# STM32.net
KiCad netlist of a schematic drawn in Altium Designer
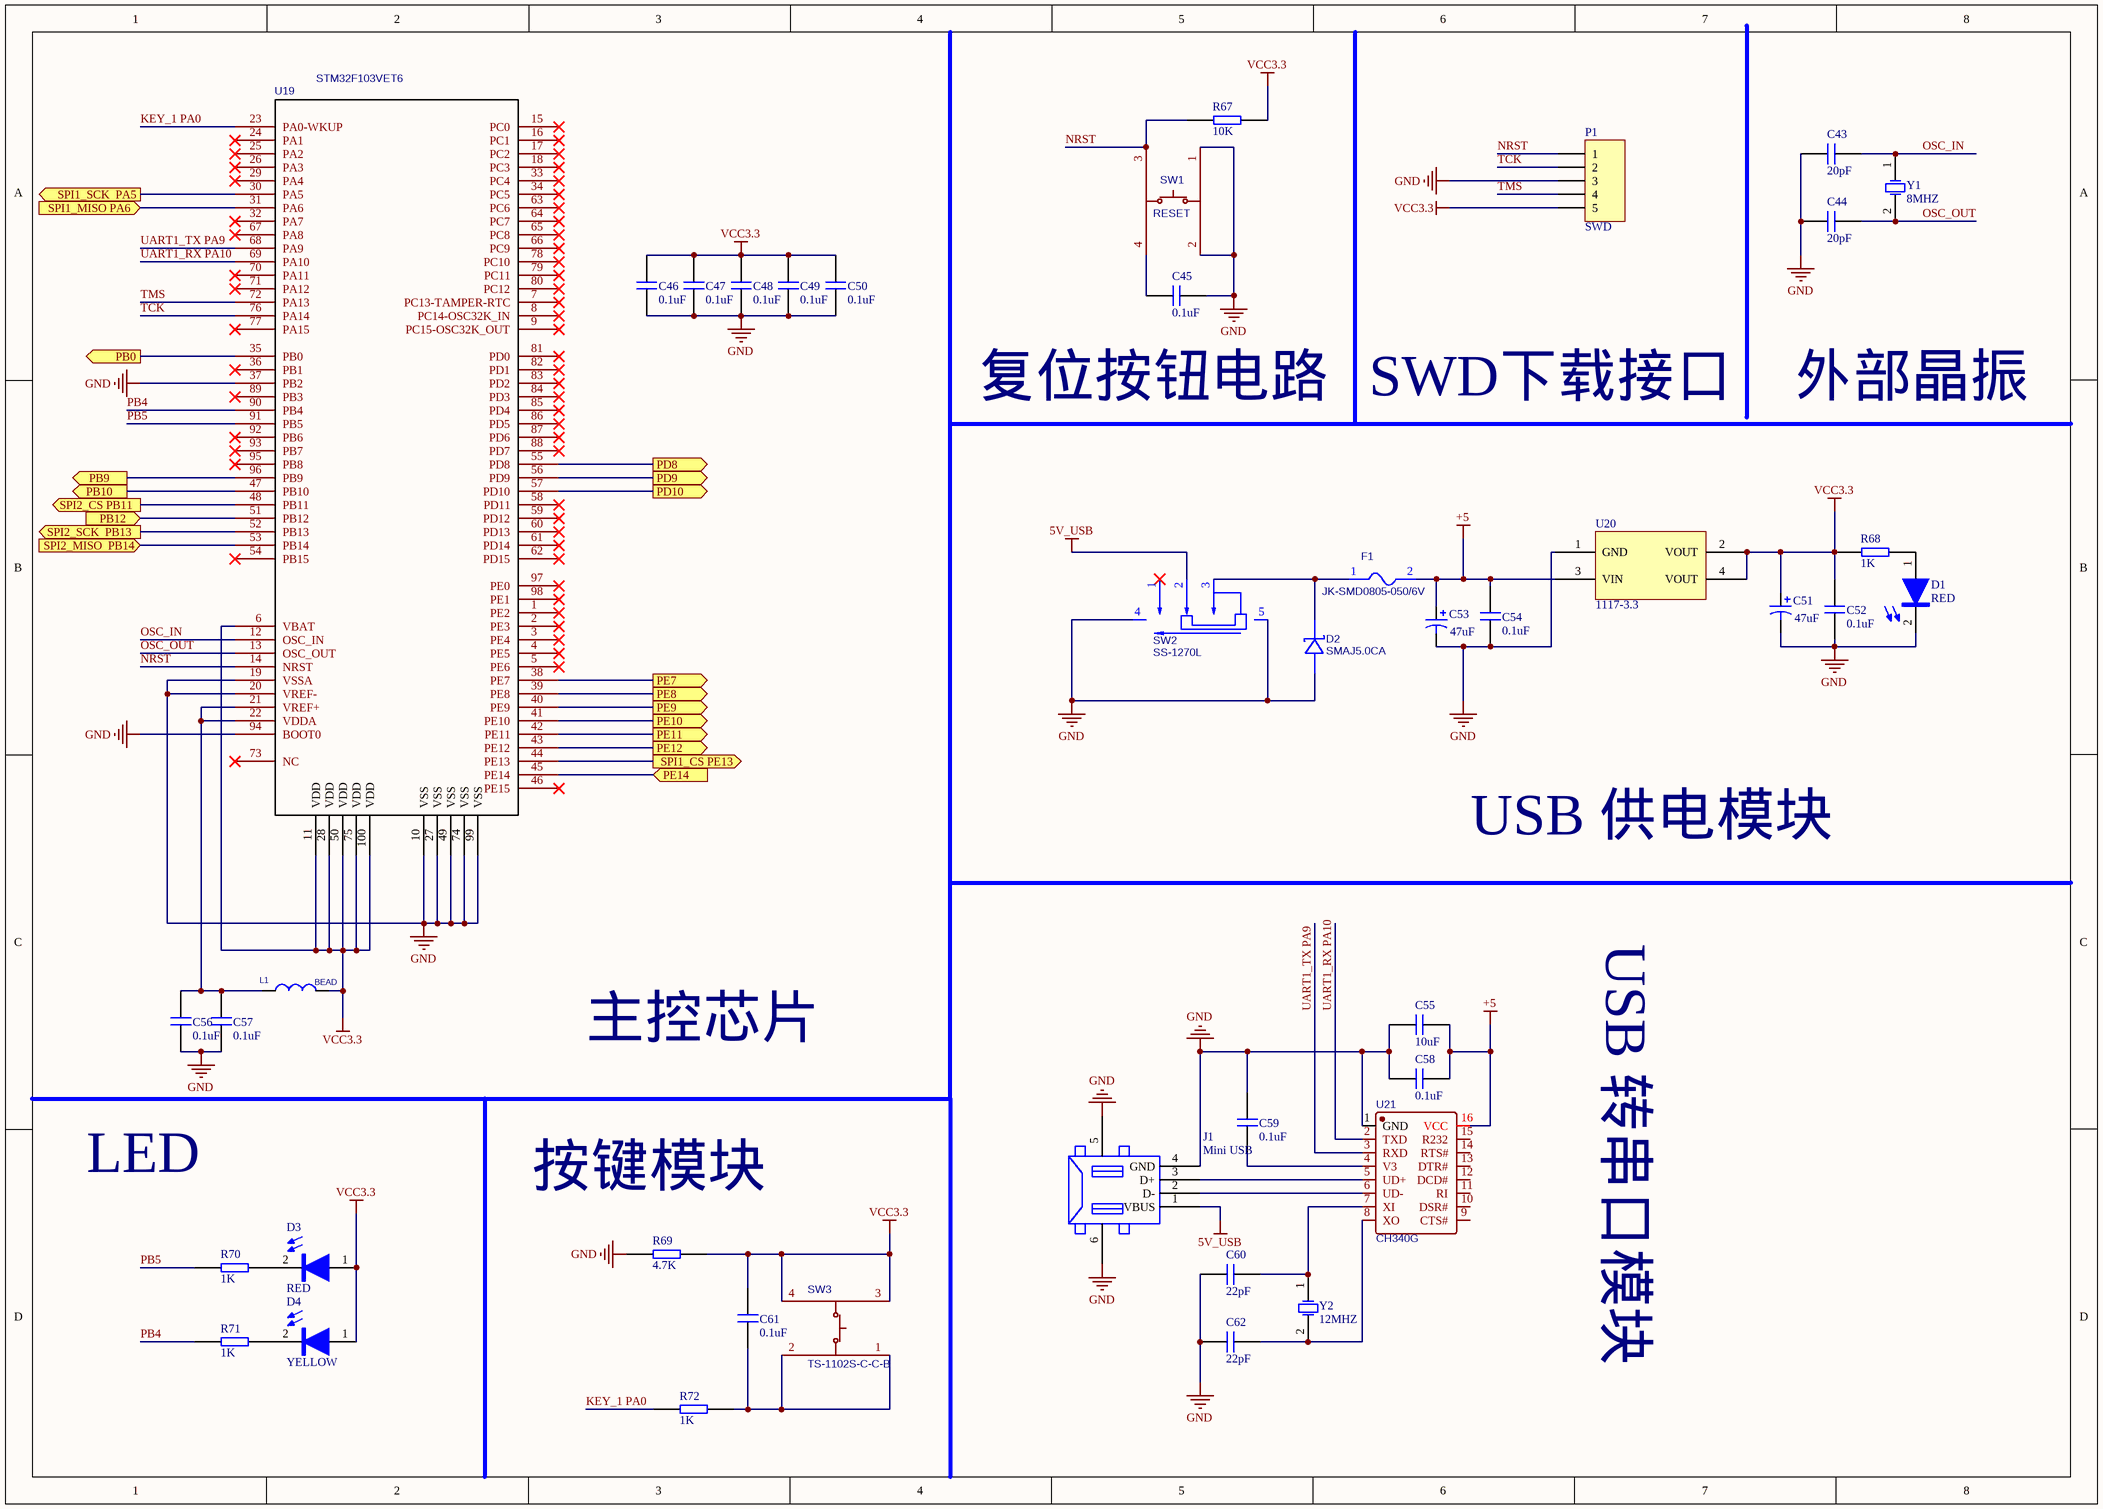
[diagram p0: STM32主控模块.SchDoc]

(export (version "E")
  (design (tool "Eeschema 10.0.6"))
  (components
    (comp (ref "C43")
      (value "20pF")
      (footprint "0805C")
      (description "NPO高频电容")
      (libsource (lib "毕业设计") (part "CAP"))
    )
    (comp (ref "C44")
      (value "20pF")
      (footprint "0805C")
      (description "NPO高频电容")
      (libsource (lib "毕业设计") (part "CAP"))
    )
    (comp (ref "C45")
      (value "0.1uF")
      (footprint "0805C")
      (description "普通电容")
      (libsource (lib "毕业设计") (part "CAP"))
    )
    (comp (ref "C46")
      (value "0.1uF")
      (footprint "0805C")
      (description "普通电容")
      (libsource (lib "毕业设计") (part "CAP"))
    )
    (comp (ref "C47")
      (value "0.1uF")
      (footprint "0805C")
      (description "普通电容")
      (libsource (lib "毕业设计") (part "CAP"))
    )
    (comp (ref "C48")
      (value "0.1uF")
      (footprint "0805C")
      (description "普通电容")
      (libsource (lib "毕业设计") (part "CAP"))
    )
    (comp (ref "C49")
      (value "0.1uF")
      (footprint "0805C")
      (description "普通电容")
      (libsource (lib "毕业设计") (part "CAP"))
    )
    (comp (ref "C50")
      (value "0.1uF")
      (footprint "0805C")
      (description "普通电容")
      (libsource (lib "毕业设计") (part "CAP"))
    )
    (comp (ref "C51")
      (value "47uF")
      (footprint "CAP-SMD_BD6.3-L6.6-W6.6-LS7.2-FD")
      (description "Polarized Capacitor (Radial)")
      (fields (field (name "Comment") "Cap Pol1") (field (name "PUBLISHER") "Altium Limited"))
      (libsource (lib "Miscellaneous Devices") (part "Cap Pol1"))
    )
    (comp (ref "C52")
      (value "0.1uF")
      (footprint "0805C")
      (description "普通电容")
      (libsource (lib "毕业设计") (part "CAP"))
    )
    (comp (ref "C53")
      (value "47uF")
      (footprint "CAP-SMD_BD6.3-L6.6-W6.6-LS7.2-FD")
      (description "Polarized Capacitor (Radial)")
      (fields (field (name "Comment") "Cap Pol1") (field (name "PUBLISHER") "Altium Limited"))
      (libsource (lib "Miscellaneous Devices") (part "Cap Pol1"))
    )
    (comp (ref "C54")
      (value "0.1uF")
      (footprint "0805C")
      (description "普通电容")
      (libsource (lib "毕业设计") (part "CAP"))
    )
    (comp (ref "C55")
      (value "10uF")
      (footprint "0805C")
      (description "普通电容")
      (libsource (lib "毕业设计") (part "CAP"))
    )
    (comp (ref "C56")
      (value "0.1uF")
      (footprint "0805C")
      (description "普通电容")
      (libsource (lib "毕业设计") (part "CAP"))
    )
    (comp (ref "C57")
      (value "0.1uF")
      (footprint "0805C")
      (description "普通电容")
      (libsource (lib "毕业设计") (part "CAP"))
    )
    (comp (ref "C58")
      (value "0.1uF")
      (footprint "0805C")
      (description "普通电容")
      (libsource (lib "毕业设计") (part "CAP"))
    )
    (comp (ref "C59")
      (value "0.1uF")
      (footprint "0805C")
      (description "普通电容")
      (libsource (lib "毕业设计") (part "CAP"))
    )
    (comp (ref "C60")
      (value "22pF")
      (footprint "0603C")
      (description "普通电容")
      (libsource (lib "毕业设计") (part "CAP"))
    )
    (comp (ref "C61")
      (value "0.1uF")
      (footprint "0805C")
      (description "普通电容")
      (libsource (lib "毕业设计") (part "CAP"))
    )
    (comp (ref "C62")
      (value "22pF")
      (footprint "0603C")
      (description "普通电容")
      (libsource (lib "毕业设计") (part "CAP"))
    )
    (comp (ref "D1")
      (value "RED")
      (footprint "LED0603")
      (description "发光二极管")
      (libsource (lib "毕业设计") (part "LED"))
    )
    (comp (ref "D2")
      (value "SMAJ5.0CA")
      (footprint "SMA_L4.4-W2.6-LS5.0-RD")
      (description "稳压二极管")
      (fields (field (name "BOM_SUPPLIER PART") "C116601"))
      (libsource (lib "毕业设计") (part "SMAJ5.0CA_C116601"))
    )
    (comp (ref "D3")
      (value "RED")
      (footprint "LED0603")
      (description "发光二极管")
      (libsource (lib "毕业设计") (part "LED"))
    )
    (comp (ref "D4")
      (value "YELLOW")
      (footprint "LED0603")
      (description "发光二极管")
      (libsource (lib "毕业设计") (part "LED"))
    )
    (comp (ref "F1")
      (value "JK-SMD0805-050/6V")
      (footprint "F0805")
      (description "500mA 保险丝")
      (fields (field (name "BOM_SUPPLIER PART") "C2830231") (field (name "CONTRIBUTOR") "LCSC"))
      (libsource (lib "毕业设计") (part "JK-SMD0805-050/6V"))
    )
    (comp (ref "J1")
      (value "Mini USB")
      (footprint "USB-B-TH_U241-041N-1BR85-1")
      (description "Mini A型USB母座")
      (libsource (lib "毕业设计") (part "Mini-B USB H"))
    )
    (comp (ref "L1")
      (value "BEAD")
      (footprint "L0603")
      (description "0603,BEAD")
      (fields (field (name "Comment") "BEAD-220/100MHZ-0603"))
      (libsource (lib "毕业设计") (part "BEAD-220/100MHZ-0603"))
    )
    (comp (ref "P1")
      (value "SWD")
      (footprint "HDR1X5")
      (description "Header, 5-Pin")
      (fields (field (name "PUBLISHER") "Altium Limited"))
      (libsource (lib "Miscellaneous Connectors") (part "Header 5"))
    )
    (comp (ref "R67")
      (value "10K")
      (footprint "0603R")
      (description "电阻模型")
      (libsource (lib "毕业设计") (part "RES"))
    )
    (comp (ref "R68")
      (value "1K")
      (footprint "0805R")
      (description "电阻模型")
      (libsource (lib "毕业设计") (part "RES"))
    )
    (comp (ref "R69")
      (value "4.7K")
      (footprint "0603R")
      (description "电阻模型")
      (libsource (lib "毕业设计") (part "RES"))
    )
    (comp (ref "R70")
      (value "1K")
      (footprint "0805R")
      (description "电阻模型")
      (libsource (lib "毕业设计") (part "RES"))
    )
    (comp (ref "R71")
      (value "1K")
      (footprint "0805R")
      (description "电阻模型")
      (libsource (lib "毕业设计") (part "RES"))
    )
    (comp (ref "R72")
      (value "1K")
      (footprint "0805R")
      (description "电阻模型")
      (libsource (lib "毕业设计") (part "RES"))
    )
    (comp (ref "SW1")
      (value "RESET")
      (footprint "KEY-SMD_4P-L6.0-W6.0-P4.50-LS9.5-BL")
      (description "轻触开关")
      (fields
        (field (name "BOM_SUPPLIER PART") "C381039")
        (field (name "BOM_MANUFACTURER PART") "TS-1102S-C-C-B")
        (field (name "CONTRIBUTOR") "LCSC")
      )
      (libsource (lib "毕业设计") (part "SW-PB"))
    )
    (comp (ref "SW2")
      (value "SS-1270L")
      (footprint "SW-TH_SLD-12-501")
      (description "拨动开关")
      (fields (field (name "BOM_SUPPLIER PART") "C589300") (field (name "CONTRIBUTOR") "LCSC"))
      (libsource (lib "毕业设计") (part "SS-1270L"))
    )
    (comp (ref "SW3")
      (value "TS-1102S-C-C-B")
      (footprint "KEY-SMD_4P-L6.0-W6.0-P4.50-LS9.5-BL")
      (description "轻触开关")
      (fields (field (name "BOM_SUPPLIER PART") "C381039") (field (name "CONTRIBUTOR") "LCSC"))
      (libsource (lib "毕业设计") (part "SW-PB"))
    )
    (comp (ref "U19")
      (value "STM32F103VET6")
      (footprint "STM32F103VET6-LQFP")
      (fields (field (name "BOM_SUPPLIER PART") "C8308"))
      (libsource (lib "毕业设计") (part "STM32F103VET6"))
    )
    (comp (ref "U20")
      (value "1117-3.3")
      (footprint "SOT230P700X190-4N")
      (description "线性稳压芯片")
      (libsource (lib "毕业设计") (part "AMS1117-3.3"))
    )
    (comp (ref "U21")
      (value "CH340G")
      (footprint "SOIC-16_L9.9-W3.9-P1.27-LS6.0-BL")
      (description "USB转TTL芯片")
      (fields (field (name "BOM_SUPPLIER PART") "C14267"))
      (libsource (lib "毕业设计") (part "CH340G"))
    )
    (comp (ref "Y1")
      (value "8MHZ")
      (footprint "49SMD")
      (description "Crystal Oscillator")
      (fields (field (name "PUBLISHER") "Altium Limited"))
      (libsource (lib "Miscellaneous Devices") (part "XTAL"))
    )
    (comp (ref "Y2")
      (value "12MHZ")
      (footprint "HC-49US_L11.5-W4.5-P4.88")
      (description "Crystal Oscillator")
      (fields (field (name "PUBLISHER") "Altium Limited"))
      (libsource (lib "Miscellaneous Devices") (part "XTAL"))
    )
  )
  (nets
    (net (code "1") (name "+5") (class "Default")
      (node (ref "C53") (pin "1") (pinfunction "1_1") (pintype "passive"))
      (node (ref "C54") (pin "2") (pinfunction "2_2") (pintype "passive"))
      (node (ref "C55") (pin "1") (pinfunction "1_1") (pintype "passive"))
      (node (ref "C58") (pin "2") (pinfunction "2_2") (pintype "passive"))
      (node (ref "F1") (pin "2") (pinfunction "2_2") (pintype "passive"))
      (node (ref "U20") (pin "3") (pinfunction "VIN_3") (pintype "passive"))
      (node (ref "U21") (pin "16") (pinfunction "VCC_16") (pintype "passive"))
    )
    (net (code "2") (name "/KEY_1 PA0") (class "Default")
      (node (ref "R72") (pin "1") (pinfunction "1_1") (pintype "passive"))
      (node (ref "U19") (pin "23") (pinfunction "PA0-WKUP_23") (pintype "passive"))
    )
    (net (code "3") (name "/NRST") (class "Default")
      (node (ref "P1") (pin "1") (pinfunction "1_1") (pintype "passive"))
      (node (ref "R67") (pin "1") (pinfunction "1_1") (pintype "passive"))
      (node (ref "SW1") (pin "3") (pinfunction "3_3") (pintype "passive"))
      (node (ref "U19") (pin "14") (pinfunction "NRST_14") (pintype "passive"))
    )
    (net (code "4") (name "/OSC_IN") (class "Default")
      (node (ref "C43") (pin "2") (pinfunction "2_2") (pintype "passive"))
      (node (ref "U19") (pin "12") (pinfunction "OSC_IN_12") (pintype "passive"))
      (node (ref "Y1") (pin "1") (pinfunction "OSC1_1") (pintype "passive"))
    )
    (net (code "5") (name "/OSC_OUT") (class "Default")
      (node (ref "C44") (pin "2") (pinfunction "2_2") (pintype "passive"))
      (node (ref "U19") (pin "13") (pinfunction "OSC_OUT_13") (pintype "passive"))
      (node (ref "Y1") (pin "2") (pinfunction "OSC2_2") (pintype "passive"))
    )
    (net (code "6") (name "/PB0") (class "Default")
      (node (ref "U19") (pin "35") (pinfunction "PB0_35") (pintype "passive"))
    )
    (net (code "7") (name "/PB4") (class "Default")
      (node (ref "R71") (pin "1") (pinfunction "1_1") (pintype "passive"))
      (node (ref "U19") (pin "90") (pinfunction "PB4_90") (pintype "passive"))
    )
    (net (code "8") (name "/PB5") (class "Default")
      (node (ref "R70") (pin "1") (pinfunction "1_1") (pintype "passive"))
      (node (ref "U19") (pin "91") (pinfunction "PB5_91") (pintype "passive"))
    )
    (net (code "9") (name "/PB9") (class "Default")
      (node (ref "U19") (pin "96") (pinfunction "PB9_96") (pintype "passive"))
    )
    (net (code "10") (name "/PB10") (class "Default")
      (node (ref "U19") (pin "47") (pinfunction "PB10_47") (pintype "passive"))
    )
    (net (code "11") (name "/PB12") (class "Default")
      (node (ref "U19") (pin "51") (pinfunction "PB12_51") (pintype "passive"))
    )
    (net (code "12") (name "/PD8") (class "Default")
      (node (ref "U19") (pin "55") (pinfunction "PD8_55") (pintype "passive"))
    )
    (net (code "13") (name "/PD9") (class "Default")
      (node (ref "U19") (pin "56") (pinfunction "PD9_56") (pintype "passive"))
    )
    (net (code "14") (name "/PD10") (class "Default")
      (node (ref "U19") (pin "57") (pinfunction "PD10_57") (pintype "passive"))
    )
    (net (code "15") (name "/PE7") (class "Default")
      (node (ref "U19") (pin "38") (pinfunction "PE7_38") (pintype "passive"))
    )
    (net (code "16") (name "/PE8") (class "Default")
      (node (ref "U19") (pin "39") (pinfunction "PE8_39") (pintype "passive"))
    )
    (net (code "17") (name "/PE9") (class "Default")
      (node (ref "U19") (pin "40") (pinfunction "PE9_40") (pintype "passive"))
    )
    (net (code "18") (name "/PE10") (class "Default")
      (node (ref "U19") (pin "41") (pinfunction "PE10_41") (pintype "passive"))
    )
    (net (code "19") (name "/PE11") (class "Default")
      (node (ref "U19") (pin "42") (pinfunction "PE11_42") (pintype "passive"))
    )
    (net (code "20") (name "/PE12") (class "Default")
      (node (ref "U19") (pin "43") (pinfunction "PE12_43") (pintype "passive"))
    )
    (net (code "21") (name "/PE14") (class "Default")
      (node (ref "U19") (pin "45") (pinfunction "PE14_45") (pintype "passive"))
    )
    (net (code "22") (name "/SPI1_CS PE13") (class "Default")
      (node (ref "U19") (pin "44") (pinfunction "PE13_44") (pintype "passive"))
    )
    (net (code "23") (name "/SPI1_MISO PA6") (class "Default")
      (node (ref "U19") (pin "31") (pinfunction "PA6_31") (pintype "passive"))
    )
    (net (code "24") (name "/SPI1_SCK  PA5") (class "Default")
      (node (ref "U19") (pin "30") (pinfunction "PA5_30") (pintype "passive"))
    )
    (net (code "25") (name "/SPI2_CS PB11") (class "Default")
      (node (ref "U19") (pin "48") (pinfunction "PB11_48") (pintype "passive"))
    )
    (net (code "26") (name "/SPI2_MISO  PB14") (class "Default")
      (node (ref "U19") (pin "53") (pinfunction "PB14_53") (pintype "passive"))
    )
    (net (code "27") (name "/SPI2_SCK  PB13") (class "Default")
      (node (ref "U19") (pin "52") (pinfunction "PB13_52") (pintype "passive"))
    )
    (net (code "28") (name "/TCK") (class "Default")
      (node (ref "P1") (pin "2") (pinfunction "2_2") (pintype "passive"))
      (node (ref "U19") (pin "76") (pinfunction "PA14_76") (pintype "passive"))
    )
    (net (code "29") (name "/TMS") (class "Default")
      (node (ref "P1") (pin "4") (pinfunction "4_4") (pintype "passive"))
      (node (ref "U19") (pin "72") (pinfunction "PA13_72") (pintype "passive"))
    )
    (net (code "30") (name "/UART1_RX PA10") (class "Default")
      (node (ref "U19") (pin "69") (pinfunction "PA10_69") (pintype "passive"))
      (node (ref "U21") (pin "2") (pinfunction "TXD_2") (pintype "passive"))
    )
    (net (code "31") (name "/UART1_TX PA9") (class "Default")
      (node (ref "U19") (pin "68") (pinfunction "PA9_68") (pintype "passive"))
      (node (ref "U21") (pin "3") (pinfunction "RXD_3") (pintype "passive"))
    )
    (net (code "32") (name "5V_USB") (class "Default")
      (node (ref "J1") (pin "1") (pinfunction "VBUS_1") (pintype "passive"))
      (node (ref "SW2") (pin "2") (pinfunction "2_2") (pintype "passive"))
    )
    (net (code "33") (name "GND") (class "Default")
      (node (ref "C43") (pin "1") (pinfunction "1_1") (pintype "passive"))
      (node (ref "C44") (pin "1") (pinfunction "1_1") (pintype "passive"))
      (node (ref "C45") (pin "2") (pinfunction "2_2") (pintype "passive"))
      (node (ref "C46") (pin "1") (pinfunction "1_1") (pintype "passive"))
      (node (ref "C47") (pin "1") (pinfunction "1_1") (pintype "passive"))
      (node (ref "C48") (pin "1") (pinfunction "1_1") (pintype "passive"))
      (node (ref "C49") (pin "1") (pinfunction "1_1") (pintype "passive"))
      (node (ref "C50") (pin "1") (pinfunction "1_1") (pintype "passive"))
      (node (ref "C51") (pin "2") (pinfunction "2_2") (pintype "passive"))
      (node (ref "C52") (pin "1") (pinfunction "1_1") (pintype "passive"))
      (node (ref "C53") (pin "2") (pinfunction "2_2") (pintype "passive"))
      (node (ref "C54") (pin "1") (pinfunction "1_1") (pintype "passive"))
      (node (ref "C55") (pin "2") (pinfunction "2_2") (pintype "passive"))
      (node (ref "C56") (pin "1") (pinfunction "1_1") (pintype "passive"))
      (node (ref "C57") (pin "1") (pinfunction "1_1") (pintype "passive"))
      (node (ref "C58") (pin "1") (pinfunction "1_1") (pintype "passive"))
      (node (ref "C59") (pin "1") (pinfunction "1_1") (pintype "passive"))
      (node (ref "C60") (pin "1") (pinfunction "1_1") (pintype "passive"))
      (node (ref "C62") (pin "1") (pinfunction "1_1") (pintype "passive"))
      (node (ref "D1") (pin "2") (pinfunction "2_2") (pintype "passive"))
      (node (ref "D2") (pin "2") (pinfunction "A_2") (pintype "passive"))
      (node (ref "J1") (pin "4") (pinfunction "GND_4") (pintype "passive"))
      (node (ref "J1") (pin "5") (pintype "passive"))
      (node (ref "J1") (pin "6") (pintype "passive"))
      (node (ref "P1") (pin "3") (pinfunction "3_3") (pintype "passive"))
      (node (ref "R69") (pin "1") (pinfunction "1_1") (pintype "passive"))
      (node (ref "SW1") (pin "1") (pinfunction "1_1") (pintype "passive"))
      (node (ref "SW1") (pin "2") (pinfunction "2_2") (pintype "passive"))
      (node (ref "SW2") (pin "4") (pinfunction "4_4") (pintype "passive"))
      (node (ref "SW2") (pin "5") (pinfunction "5_5") (pintype "passive"))
      (node (ref "U19") (pin "10") (pinfunction "VSS_10") (pintype "passive"))
      (node (ref "U19") (pin "19") (pinfunction "VSSA_19") (pintype "passive"))
      (node (ref "U19") (pin "20") (pinfunction "VREF-_20") (pintype "passive"))
      (node (ref "U19") (pin "27") (pinfunction "VSS_27") (pintype "passive"))
      (node (ref "U19") (pin "37") (pinfunction "PB2_37") (pintype "passive"))
      (node (ref "U19") (pin "49") (pinfunction "VSS_49") (pintype "passive"))
      (node (ref "U19") (pin "74") (pinfunction "VSS_74") (pintype "passive"))
      (node (ref "U19") (pin "94") (pinfunction "BOOT0_94") (pintype "passive"))
      (node (ref "U19") (pin "99") (pinfunction "VSS_99") (pintype "passive"))
      (node (ref "U20") (pin "1") (pinfunction "GND_1") (pintype "passive"))
      (node (ref "U21") (pin "1") (pinfunction "GND_1") (pintype "passive"))
    )
    (net (code "34") (name "Net-(C45-Pad1)") (class "Default")
      (node (ref "C45") (pin "1") (pinfunction "1_1") (pintype "passive"))
      (node (ref "SW1") (pin "4") (pinfunction "4_4") (pintype "passive"))
    )
    (net (code "35") (name "Net-(C61-Pad1)") (class "Default")
      (node (ref "C61") (pin "1") (pinfunction "1_1") (pintype "passive"))
      (node (ref "R72") (pin "2") (pinfunction "2_2") (pintype "passive"))
      (node (ref "SW3") (pin "1") (pinfunction "1_1") (pintype "passive"))
      (node (ref "SW3") (pin "2") (pinfunction "2_2") (pintype "passive"))
    )
    (net (code "36") (name "Net-(D1-Pad1)") (class "Default")
      (node (ref "D1") (pin "1") (pinfunction "1_1") (pintype "passive"))
      (node (ref "R68") (pin "2") (pinfunction "2_2") (pintype "passive"))
    )
    (net (code "37") (name "Net-(D2-K)") (class "Default")
      (node (ref "D2") (pin "1") (pinfunction "K_1") (pintype "passive"))
      (node (ref "F1") (pin "1") (pinfunction "1_1") (pintype "passive"))
      (node (ref "SW2") (pin "3") (pinfunction "3_3") (pintype "passive"))
    )
    (net (code "38") (name "Net-(D3-Pad2)") (class "Default")
      (node (ref "D3") (pin "2") (pinfunction "2_2") (pintype "passive"))
      (node (ref "R70") (pin "2") (pinfunction "2_2") (pintype "passive"))
    )
    (net (code "39") (name "Net-(D4-Pad2)") (class "Default")
      (node (ref "D4") (pin "2") (pinfunction "2_2") (pintype "passive"))
      (node (ref "R71") (pin "2") (pinfunction "2_2") (pintype "passive"))
    )
    (net (code "40") (name "Net-(J1-D+)") (class "Default")
      (node (ref "J1") (pin "3") (pinfunction "D+_3") (pintype "passive"))
      (node (ref "U21") (pin "5") (pinfunction "UD+_5") (pintype "passive"))
    )
    (net (code "41") (name "Net-(J1-D-)") (class "Default")
      (node (ref "J1") (pin "2") (pinfunction "D-_2") (pintype "passive"))
      (node (ref "U21") (pin "6") (pinfunction "UD-_6") (pintype "passive"))
    )
    (net (code "42") (name "Net-(U19-VDDA)") (class "Default")
      (node (ref "C56") (pin "2") (pinfunction "2_2") (pintype "passive"))
      (node (ref "C57") (pin "2") (pinfunction "2_2") (pintype "passive"))
      (node (ref "L1") (pin "1") (pinfunction "1_1") (pintype "passive"))
      (node (ref "U19") (pin "21") (pinfunction "VREF+_21") (pintype "passive"))
      (node (ref "U19") (pin "22") (pinfunction "VDDA_22") (pintype "passive"))
    )
    (net (code "43") (name "Net-(U21-V3)") (class "Default")
      (node (ref "C59") (pin "2") (pinfunction "2_2") (pintype "passive"))
      (node (ref "U21") (pin "4") (pinfunction "V3_4") (pintype "passive"))
    )
    (net (code "44") (name "Net-(U21-XI)") (class "Default")
      (node (ref "C60") (pin "2") (pinfunction "2_2") (pintype "passive"))
      (node (ref "U21") (pin "7") (pinfunction "XI_7") (pintype "passive"))
      (node (ref "Y2") (pin "1") (pinfunction "OSC1_1") (pintype "passive"))
    )
    (net (code "45") (name "Net-(U21-XO)") (class "Default")
      (node (ref "C62") (pin "2") (pinfunction "2_2") (pintype "passive"))
      (node (ref "U21") (pin "8") (pinfunction "XO_8") (pintype "passive"))
      (node (ref "Y2") (pin "2") (pinfunction "OSC2_2") (pintype "passive"))
    )
    (net (code "46") (name "VCC3.3") (class "Default")
      (node (ref "C46") (pin "2") (pinfunction "2_2") (pintype "passive"))
      (node (ref "C47") (pin "2") (pinfunction "2_2") (pintype "passive"))
      (node (ref "C48") (pin "2") (pinfunction "2_2") (pintype "passive"))
      (node (ref "C49") (pin "2") (pinfunction "2_2") (pintype "passive"))
      (node (ref "C50") (pin "2") (pinfunction "2_2") (pintype "passive"))
      (node (ref "C51") (pin "1") (pinfunction "1_1") (pintype "passive"))
      (node (ref "C52") (pin "2") (pinfunction "2_2") (pintype "passive"))
      (node (ref "C61") (pin "2") (pinfunction "2_2") (pintype "passive"))
      (node (ref "D3") (pin "1") (pinfunction "1_1") (pintype "passive"))
      (node (ref "D4") (pin "1") (pinfunction "1_1") (pintype "passive"))
      (node (ref "L1") (pin "2") (pinfunction "2_2") (pintype "passive"))
      (node (ref "P1") (pin "5") (pinfunction "5_5") (pintype "passive"))
      (node (ref "R67") (pin "2") (pinfunction "2_2") (pintype "passive"))
      (node (ref "R68") (pin "1") (pinfunction "1_1") (pintype "passive"))
      (node (ref "R69") (pin "2") (pinfunction "2_2") (pintype "passive"))
      (node (ref "SW3") (pin "3") (pinfunction "3_3") (pintype "passive"))
      (node (ref "SW3") (pin "4") (pinfunction "4_4") (pintype "passive"))
      (node (ref "U19") (pin "100") (pinfunction "VDD_100") (pintype "passive"))
      (node (ref "U19") (pin "11") (pinfunction "VDD_11") (pintype "passive"))
      (node (ref "U19") (pin "28") (pinfunction "VDD_28") (pintype "passive"))
      (node (ref "U19") (pin "50") (pinfunction "VDD_50") (pintype "passive"))
      (node (ref "U19") (pin "6") (pinfunction "VBAT_6") (pintype "passive"))
      (node (ref "U19") (pin "75") (pinfunction "VDD_75") (pintype "passive"))
      (node (ref "U20") (pin "2") (pinfunction "VOUT_2") (pintype "passive"))
      (node (ref "U20") (pin "4") (pinfunction "VOUT_4") (pintype "passive"))
    )
    (net (code "47") (name "unconnected-(SW2-Pad1)") (class "Default")
      (node (ref "SW2") (pin "1") (pinfunction "1_1") (pintype "passive+no_connect"))
    )
    (net (code "48") (name "unconnected-(U19-NC-Pad73)") (class "Default")
      (node (ref "U19") (pin "73") (pinfunction "NC_73") (pintype "passive+no_connect"))
    )
    (net (code "49") (name "unconnected-(U19-PA1-Pad24)") (class "Default")
      (node (ref "U19") (pin "24") (pinfunction "PA1_24") (pintype "passive+no_connect"))
    )
    (net (code "50") (name "unconnected-(U19-PA2-Pad25)") (class "Default")
      (node (ref "U19") (pin "25") (pinfunction "PA2_25") (pintype "passive+no_connect"))
    )
    (net (code "51") (name "unconnected-(U19-PA3-Pad26)") (class "Default")
      (node (ref "U19") (pin "26") (pinfunction "PA3_26") (pintype "passive+no_connect"))
    )
    (net (code "52") (name "unconnected-(U19-PA4-Pad29)") (class "Default")
      (node (ref "U19") (pin "29") (pinfunction "PA4_29") (pintype "passive+no_connect"))
    )
    (net (code "53") (name "unconnected-(U19-PA7-Pad32)") (class "Default")
      (node (ref "U19") (pin "32") (pinfunction "PA7_32") (pintype "passive+no_connect"))
    )
    (net (code "54") (name "unconnected-(U19-PA8-Pad67)") (class "Default")
      (node (ref "U19") (pin "67") (pinfunction "PA8_67") (pintype "passive+no_connect"))
    )
    (net (code "55") (name "unconnected-(U19-PA11-Pad70)") (class "Default")
      (node (ref "U19") (pin "70") (pinfunction "PA11_70") (pintype "passive+no_connect"))
    )
    (net (code "56") (name "unconnected-(U19-PA12-Pad71)") (class "Default")
      (node (ref "U19") (pin "71") (pinfunction "PA12_71") (pintype "passive+no_connect"))
    )
    (net (code "57") (name "unconnected-(U19-PA15-Pad77)") (class "Default")
      (node (ref "U19") (pin "77") (pinfunction "PA15_77") (pintype "passive+no_connect"))
    )
    (net (code "58") (name "unconnected-(U19-PB1-Pad36)") (class "Default")
      (node (ref "U19") (pin "36") (pinfunction "PB1_36") (pintype "passive+no_connect"))
    )
    (net (code "59") (name "unconnected-(U19-PB3-Pad89)") (class "Default")
      (node (ref "U19") (pin "89") (pinfunction "PB3_89") (pintype "passive+no_connect"))
    )
    (net (code "60") (name "unconnected-(U19-PB6-Pad92)") (class "Default")
      (node (ref "U19") (pin "92") (pinfunction "PB6_92") (pintype "passive+no_connect"))
    )
    (net (code "61") (name "unconnected-(U19-PB7-Pad93)") (class "Default")
      (node (ref "U19") (pin "93") (pinfunction "PB7_93") (pintype "passive+no_connect"))
    )
    (net (code "62") (name "unconnected-(U19-PB8-Pad95)") (class "Default")
      (node (ref "U19") (pin "95") (pinfunction "PB8_95") (pintype "passive+no_connect"))
    )
    (net (code "63") (name "unconnected-(U19-PB15-Pad54)") (class "Default")
      (node (ref "U19") (pin "54") (pinfunction "PB15_54") (pintype "passive+no_connect"))
    )
    (net (code "64") (name "unconnected-(U19-PC0-Pad15)") (class "Default")
      (node (ref "U19") (pin "15") (pinfunction "PC0_15") (pintype "passive+no_connect"))
    )
    (net (code "65") (name "unconnected-(U19-PC1-Pad16)") (class "Default")
      (node (ref "U19") (pin "16") (pinfunction "PC1_16") (pintype "passive+no_connect"))
    )
    (net (code "66") (name "unconnected-(U19-PC2-Pad17)") (class "Default")
      (node (ref "U19") (pin "17") (pinfunction "PC2_17") (pintype "passive+no_connect"))
    )
    (net (code "67") (name "unconnected-(U19-PC3-Pad18)") (class "Default")
      (node (ref "U19") (pin "18") (pinfunction "PC3_18") (pintype "passive+no_connect"))
    )
    (net (code "68") (name "unconnected-(U19-PC4-Pad33)") (class "Default")
      (node (ref "U19") (pin "33") (pinfunction "PC4_33") (pintype "passive+no_connect"))
    )
    (net (code "69") (name "unconnected-(U19-PC5-Pad34)") (class "Default")
      (node (ref "U19") (pin "34") (pinfunction "PC5_34") (pintype "passive+no_connect"))
    )
    (net (code "70") (name "unconnected-(U19-PC6-Pad63)") (class "Default")
      (node (ref "U19") (pin "63") (pinfunction "PC6_63") (pintype "passive+no_connect"))
    )
    (net (code "71") (name "unconnected-(U19-PC7-Pad64)") (class "Default")
      (node (ref "U19") (pin "64") (pinfunction "PC7_64") (pintype "passive+no_connect"))
    )
    (net (code "72") (name "unconnected-(U19-PC8-Pad65)") (class "Default")
      (node (ref "U19") (pin "65") (pinfunction "PC8_65") (pintype "passive+no_connect"))
    )
    (net (code "73") (name "unconnected-(U19-PC9-Pad66)") (class "Default")
      (node (ref "U19") (pin "66") (pinfunction "PC9_66") (pintype "passive+no_connect"))
    )
    (net (code "74") (name "unconnected-(U19-PC10-Pad78)") (class "Default")
      (node (ref "U19") (pin "78") (pinfunction "PC10_78") (pintype "passive+no_connect"))
    )
    (net (code "75") (name "unconnected-(U19-PC11-Pad79)") (class "Default")
      (node (ref "U19") (pin "79") (pinfunction "PC11_79") (pintype "passive+no_connect"))
    )
    (net (code "76") (name "unconnected-(U19-PC12-Pad80)") (class "Default")
      (node (ref "U19") (pin "80") (pinfunction "PC12_80") (pintype "passive+no_connect"))
    )
    (net (code "77") (name "unconnected-(U19-PC13-TAMPER-RTC-Pad7)") (class "Default")
      (node (ref "U19") (pin "7") (pinfunction "PC13-TAMPER-RTC_7") (pintype "passive+no_connect"))
    )
    (net (code "78") (name "unconnected-(U19-PC14-OSC32K_IN-Pad8)") (class "Default")
      (node (ref "U19") (pin "8") (pinfunction "PC14-OSC32K_IN_8") (pintype "passive+no_connect"))
    )
    (net (code "79") (name "unconnected-(U19-PC15-OSC32K_OUT-Pad9)") (class "Default")
      (node (ref "U19") (pin "9") (pinfunction "PC15-OSC32K_OUT_9") (pintype "passive+no_connect"))
    )
    (net (code "80") (name "unconnected-(U19-PD0-Pad81)") (class "Default")
      (node (ref "U19") (pin "81") (pinfunction "PD0_81") (pintype "passive+no_connect"))
    )
    (net (code "81") (name "unconnected-(U19-PD1-Pad82)") (class "Default")
      (node (ref "U19") (pin "82") (pinfunction "PD1_82") (pintype "passive+no_connect"))
    )
    (net (code "82") (name "unconnected-(U19-PD2-Pad83)") (class "Default")
      (node (ref "U19") (pin "83") (pinfunction "PD2_83") (pintype "passive+no_connect"))
    )
    (net (code "83") (name "unconnected-(U19-PD3-Pad84)") (class "Default")
      (node (ref "U19") (pin "84") (pinfunction "PD3_84") (pintype "passive+no_connect"))
    )
    (net (code "84") (name "unconnected-(U19-PD4-Pad85)") (class "Default")
      (node (ref "U19") (pin "85") (pinfunction "PD4_85") (pintype "passive+no_connect"))
    )
    (net (code "85") (name "unconnected-(U19-PD5-Pad86)") (class "Default")
      (node (ref "U19") (pin "86") (pinfunction "PD5_86") (pintype "passive+no_connect"))
    )
    (net (code "86") (name "unconnected-(U19-PD6-Pad87)") (class "Default")
      (node (ref "U19") (pin "87") (pinfunction "PD6_87") (pintype "passive+no_connect"))
    )
    (net (code "87") (name "unconnected-(U19-PD7-Pad88)") (class "Default")
      (node (ref "U19") (pin "88") (pinfunction "PD7_88") (pintype "passive+no_connect"))
    )
    (net (code "88") (name "unconnected-(U19-PD11-Pad58)") (class "Default")
      (node (ref "U19") (pin "58") (pinfunction "PD11_58") (pintype "passive+no_connect"))
    )
    (net (code "89") (name "unconnected-(U19-PD12-Pad59)") (class "Default")
      (node (ref "U19") (pin "59") (pinfunction "PD12_59") (pintype "passive+no_connect"))
    )
    (net (code "90") (name "unconnected-(U19-PD13-Pad60)") (class "Default")
      (node (ref "U19") (pin "60") (pinfunction "PD13_60") (pintype "passive+no_connect"))
    )
    (net (code "91") (name "unconnected-(U19-PD14-Pad61)") (class "Default")
      (node (ref "U19") (pin "61") (pinfunction "PD14_61") (pintype "passive+no_connect"))
    )
    (net (code "92") (name "unconnected-(U19-PD15-Pad62)") (class "Default")
      (node (ref "U19") (pin "62") (pinfunction "PD15_62") (pintype "passive+no_connect"))
    )
    (net (code "93") (name "unconnected-(U19-PE0-Pad97)") (class "Default")
      (node (ref "U19") (pin "97") (pinfunction "PE0_97") (pintype "passive+no_connect"))
    )
    (net (code "94") (name "unconnected-(U19-PE1-Pad98)") (class "Default")
      (node (ref "U19") (pin "98") (pinfunction "PE1_98") (pintype "passive+no_connect"))
    )
    (net (code "95") (name "unconnected-(U19-PE2-Pad1)") (class "Default")
      (node (ref "U19") (pin "1") (pinfunction "PE2_1") (pintype "passive+no_connect"))
    )
    (net (code "96") (name "unconnected-(U19-PE3-Pad2)") (class "Default")
      (node (ref "U19") (pin "2") (pinfunction "PE3_2") (pintype "passive+no_connect"))
    )
    (net (code "97") (name "unconnected-(U19-PE4-Pad3)") (class "Default")
      (node (ref "U19") (pin "3") (pinfunction "PE4_3") (pintype "passive+no_connect"))
    )
    (net (code "98") (name "unconnected-(U19-PE5-Pad4)") (class "Default")
      (node (ref "U19") (pin "4") (pinfunction "PE5_4") (pintype "passive+no_connect"))
    )
    (net (code "99") (name "unconnected-(U19-PE6-Pad5)") (class "Default")
      (node (ref "U19") (pin "5") (pinfunction "PE6_5") (pintype "passive+no_connect"))
    )
    (net (code "100") (name "unconnected-(U19-PE15-Pad46)") (class "Default")
      (node (ref "U19") (pin "46") (pinfunction "PE15_46") (pintype "passive+no_connect"))
    )
    (net (code "101") (name "unconnected-(U21-CTS#-Pad9)") (class "Default")
      (node (ref "U21") (pin "9") (pinfunction "CTS#_9") (pintype "passive"))
    )
    (net (code "102") (name "unconnected-(U21-DCD#-Pad12)") (class "Default")
      (node (ref "U21") (pin "12") (pinfunction "DCD#_12") (pintype "passive"))
    )
    (net (code "103") (name "unconnected-(U21-DSR#-Pad10)") (class "Default")
      (node (ref "U21") (pin "10") (pinfunction "DSR#_10") (pintype "passive"))
    )
    (net (code "104") (name "unconnected-(U21-DTR#-Pad13)") (class "Default")
      (node (ref "U21") (pin "13") (pinfunction "DTR#_13") (pintype "passive"))
    )
    (net (code "105") (name "unconnected-(U21-R232-Pad15)") (class "Default")
      (node (ref "U21") (pin "15") (pinfunction "R232_15") (pintype "passive"))
    )
    (net (code "106") (name "unconnected-(U21-RI-Pad11)") (class "Default")
      (node (ref "U21") (pin "11") (pinfunction "RI_11") (pintype "passive"))
    )
    (net (code "107") (name "unconnected-(U21-RTS#-Pad14)") (class "Default")
      (node (ref "U21") (pin "14") (pinfunction "RTS#_14") (pintype "passive"))
    )
  )
)
